# Final.net
KiCad netlist of a schematic drawn in Altium Designer
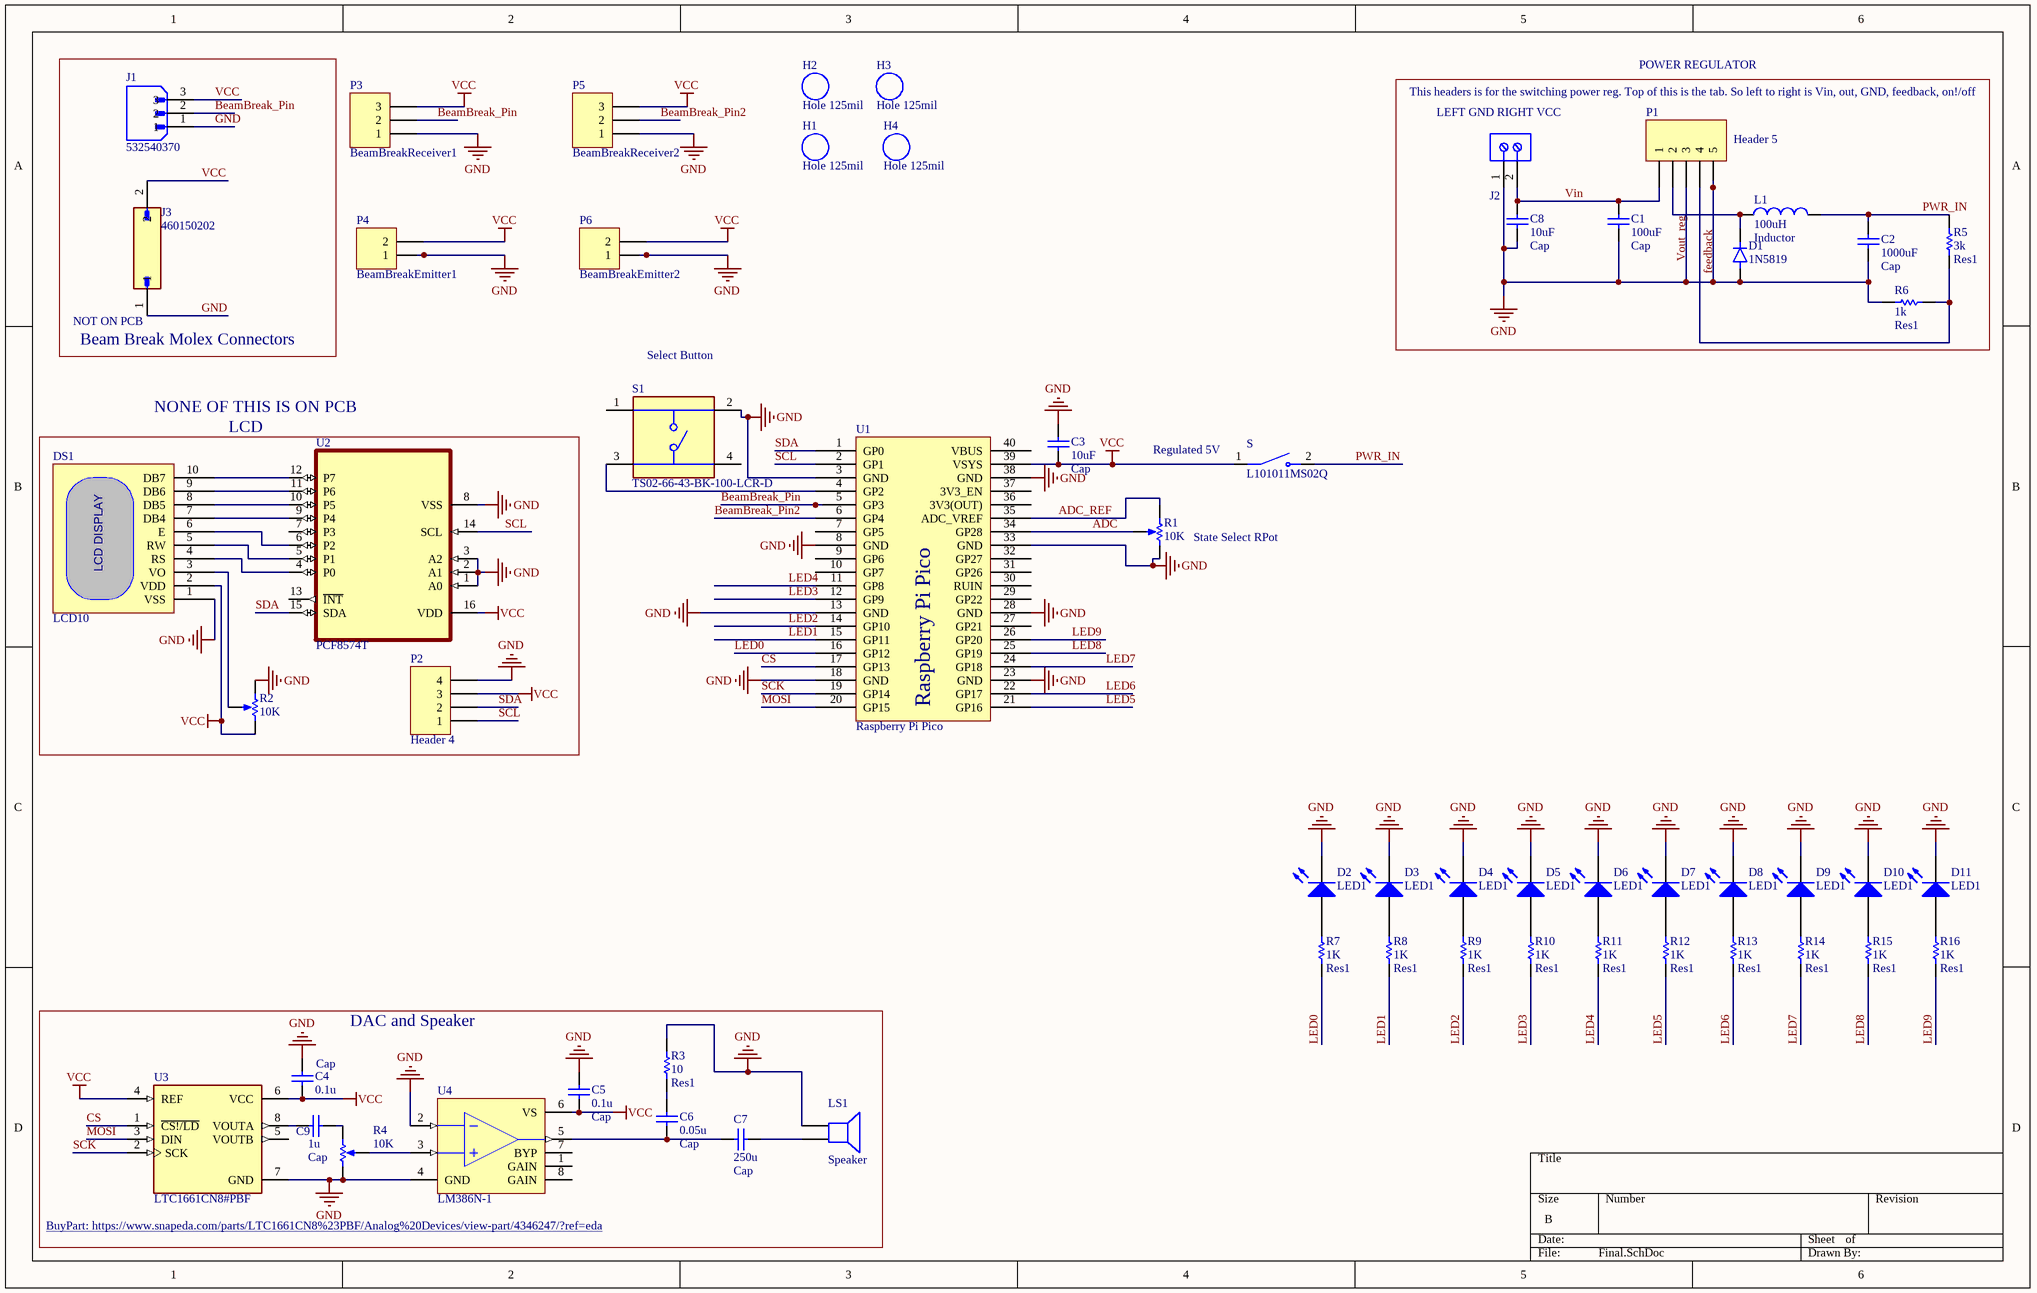
[diagram p0: Final.SchDoc]

(export (version "E")
  (design (tool "Eeschema 10.0.6"))
  (components
    (comp (ref "C1")
      (value "Cap")
      (footprint "RAD-0.3")
      (description "Capacitor")
      (fields (field (name "ALTIUM_VALUE") "100uF") (field (name "PUBLISHER") "Altium Limited"))
      (libsource (lib "Miscellaneous Devices") (part "Cap"))
    )
    (comp (ref "C2")
      (value "Cap")
      (footprint "RAD-0.3")
      (description "Capacitor")
      (fields (field (name "ALTIUM_VALUE") "1000uF") (field (name "PUBLISHER") "Altium Limited"))
      (libsource (lib "Miscellaneous Devices") (part "Cap"))
    )
    (comp (ref "C3")
      (value "Cap")
      (footprint "RAD-0.3")
      (description "Capacitor")
      (fields (field (name "ALTIUM_VALUE") "10uF") (field (name "PUBLISHER") "Altium Limited"))
      (libsource (lib "Miscellaneous Devices") (part "Cap"))
    )
    (comp (ref "C4")
      (value "Cap")
      (footprint "RAD-0.3")
      (description "Capacitor")
      (fields (field (name "ALTIUM_VALUE") "0.1u") (field (name "PUBLISHER") "Altium Limited"))
      (libsource (lib "Miscellaneous Devices") (part "Cap"))
    )
    (comp (ref "C5")
      (value "Cap")
      (footprint "RAD-0.3")
      (description "Capacitor")
      (fields (field (name "ALTIUM_VALUE") "0.1u") (field (name "PUBLISHER") "Altium Limited"))
      (libsource (lib "Miscellaneous Devices") (part "Cap"))
    )
    (comp (ref "C6")
      (value "Cap")
      (footprint "RAD-0.3")
      (description "Capacitor")
      (fields (field (name "ALTIUM_VALUE") "0.05u") (field (name "PUBLISHER") "Altium Limited"))
      (libsource (lib "Miscellaneous Devices") (part "Cap"))
    )
    (comp (ref "C7")
      (value "Cap")
      (footprint "RAD-0.3")
      (description "Capacitor")
      (fields (field (name "ALTIUM_VALUE") "250u") (field (name "PUBLISHER") "Altium Limited"))
      (libsource (lib "Miscellaneous Devices") (part "Cap"))
    )
    (comp (ref "C8")
      (value "Cap")
      (footprint "RAD-0.3")
      (description "Capacitor")
      (fields (field (name "ALTIUM_VALUE") "10uF") (field (name "PUBLISHER") "Altium Limited"))
      (libsource (lib "Miscellaneous Devices") (part "Cap"))
    )
    (comp (ref "C9")
      (value "Cap")
      (footprint "RAD-0.3")
      (description "Capacitor")
      (fields (field (name "ALTIUM_VALUE") "1u") (field (name "PUBLISHER") "Altium Limited"))
      (libsource (lib "Miscellaneous Devices") (part "Cap"))
    )
    (comp (ref "D1")
      (value "1N5819")
      (footprint "DIOAD1036W78L470D235")
      (description "1A, 40V, Planar Schottky")
      (fields (field (name "MF") "Taiwan Semiconductor"))
      (libsource (lib "1N5819") (part "1N5819"))
    )
    (comp (ref "D2")
      (value "LED1")
      (footprint "LED-1")
      (description "Typical RED GaAs LED")
      (fields (field (name "PUBLISHER") "Altium Limited"))
      (libsource (lib "Miscellaneous Devices") (part "LED1"))
    )
    (comp (ref "D3")
      (value "LED1")
      (footprint "LED-1")
      (description "Typical RED GaAs LED")
      (fields (field (name "PUBLISHER") "Altium Limited"))
      (libsource (lib "Miscellaneous Devices") (part "LED1"))
    )
    (comp (ref "D4")
      (value "LED1")
      (footprint "LED-1")
      (description "Typical RED GaAs LED")
      (fields (field (name "PUBLISHER") "Altium Limited"))
      (libsource (lib "Miscellaneous Devices") (part "LED1"))
    )
    (comp (ref "D5")
      (value "LED1")
      (footprint "LED-1")
      (description "Typical RED GaAs LED")
      (fields (field (name "PUBLISHER") "Altium Limited"))
      (libsource (lib "Miscellaneous Devices") (part "LED1"))
    )
    (comp (ref "D6")
      (value "LED1")
      (footprint "LED-1")
      (description "Typical RED GaAs LED")
      (fields (field (name "PUBLISHER") "Altium Limited"))
      (libsource (lib "Miscellaneous Devices") (part "LED1"))
    )
    (comp (ref "D7")
      (value "LED1")
      (footprint "LED-1")
      (description "Typical RED GaAs LED")
      (fields (field (name "PUBLISHER") "Altium Limited"))
      (libsource (lib "Miscellaneous Devices") (part "LED1"))
    )
    (comp (ref "D8")
      (value "LED1")
      (footprint "LED-1")
      (description "Typical RED GaAs LED")
      (fields (field (name "PUBLISHER") "Altium Limited"))
      (libsource (lib "Miscellaneous Devices") (part "LED1"))
    )
    (comp (ref "D9")
      (value "LED1")
      (footprint "LED-1")
      (description "Typical RED GaAs LED")
      (fields (field (name "PUBLISHER") "Altium Limited"))
      (libsource (lib "Miscellaneous Devices") (part "LED1"))
    )
    (comp (ref "D10")
      (value "LED1")
      (footprint "LED-1")
      (description "Typical RED GaAs LED")
      (fields (field (name "PUBLISHER") "Altium Limited"))
      (libsource (lib "Miscellaneous Devices") (part "LED1"))
    )
    (comp (ref "D11")
      (value "LED1")
      (footprint "LED-1")
      (description "Typical RED GaAs LED")
      (fields (field (name "PUBLISHER") "Altium Limited"))
      (libsource (lib "Miscellaneous Devices") (part "LED1"))
    )
    (comp (ref "DS1") (value "LCD10") (footprint "HDR1X10") (libsource (lib "ECE Lib 22") (part "LCD10")))
    (comp (ref "H1")
      (value "Hole 125mil")
      (footprint "Hole 125mil")
      (libsource (lib "ECE Lib 22") (part "Hole 125mil"))
    )
    (comp (ref "H2")
      (value "Hole 125mil")
      (footprint "Hole 125mil")
      (libsource (lib "ECE Lib 22") (part "Hole 125mil"))
    )
    (comp (ref "H3")
      (value "Hole 125mil")
      (footprint "Hole 125mil")
      (libsource (lib "ECE Lib 22") (part "Hole 125mil"))
    )
    (comp (ref "H4")
      (value "Hole 125mil")
      (footprint "Hole 125mil")
      (libsource (lib "ECE Lib 22") (part "Hole 125mil"))
    )
    (comp (ref "J1")
      (value "532540370")
      (footprint "MOLEX_532540370")
      (libsource (lib "532540370") (part "532540370"))
    )
    (comp (ref "J2")
      (value "691137710002")
      (footprint "691137710002")
      (description "WR-TBL Series 1377 Horizontal Entry, THT, pitch 5mm, 2p")
      (fields (field (name "MANUFACTURER") "Wurth Elektronik"))
      (libsource (lib "Altium_WR-TBL_rev23f") (part "691137710002"))
    )
    (comp (ref "J3")
      (value "460150202")
      (footprint "MOLEX_460150202")
      (description "Conn Power HDR 2 POS 4.2mm Solder ST Thru-Hole 2 Terminal 1 Port Mini-Fit Jr Bag")
      (libsource (lib "460150202") (part "460150202"))
    )
    (comp (ref "L1")
      (value "Inductor")
      (footprint "0402-A")
      (fields (field (name "ALTIUM_VALUE") "100uH") (field (name "PUBLISHER") "Altium Limited"))
      (libsource (lib "Miscellaneous Devices") (part "Inductor"))
    )
    (comp (ref "LS1")
      (value "Speaker")
      (footprint "PIN2")
      (description "Loudspeaker")
      (fields (field (name "PUBLISHER") "Altium Limited"))
      (libsource (lib "Miscellaneous Devices") (part "Speaker"))
    )
    (comp (ref "P1")
      (value "Header 5")
      (footprint "HDR1X5")
      (description "Header, 5-Pin")
      (fields (field (name "PUBLISHER") "Altium Limited"))
      (libsource (lib "Miscellaneous Connectors") (part "Header 5"))
    )
    (comp (ref "P2")
      (value "Header 4")
      (footprint "HDR1X4")
      (description "Header, 4-Pin")
      (fields (field (name "PUBLISHER") "Altium Limited"))
      (libsource (lib "Miscellaneous Connectors") (part "Header 4"))
    )
    (comp (ref "P3")
      (value "BeamBreakReceiver1")
      (footprint "HDR1X3")
      (description "Header, 3-Pin")
      (fields (field (name "PUBLISHER") "Altium Limited"))
      (libsource (lib "Miscellaneous Connectors") (part "Header 3"))
    )
    (comp (ref "P4")
      (value "BeamBreakEmitter1")
      (footprint "HDR1X2H")
      (description "Header, 2-Pin, Right Angle")
      (fields (field (name "PUBLISHER") "Altium Limited"))
      (libsource (lib "Miscellaneous Connectors") (part "Header 2H"))
    )
    (comp (ref "P5")
      (value "BeamBreakReceiver2")
      (footprint "HDR1X3")
      (description "Header, 3-Pin")
      (fields (field (name "PUBLISHER") "Altium Limited"))
      (libsource (lib "Miscellaneous Connectors") (part "Header 3"))
    )
    (comp (ref "P6")
      (value "BeamBreakEmitter2")
      (footprint "HDR1X2H")
      (description "Header, 2-Pin, Right Angle")
      (fields (field (name "PUBLISHER") "Altium Limited"))
      (libsource (lib "Miscellaneous Connectors") (part "Header 2H"))
    )
    (comp (ref "R1")
      (value "10K")
      (footprint "POT inline wide")
      (description "Potentiometer")
      (fields (field (name "Comment") "RPot_1") (field (name "PUBLISHER") "Altium Limited"))
      (libsource (lib "ECE Lib 22") (part "RPot_3"))
    )
    (comp (ref "R2")
      (value "10K")
      (footprint "POT OFFSET 200")
      (description "Potentiometer")
      (fields (field (name "Comment") "RPot_3") (field (name "PUBLISHER") "Altium Limited"))
      (libsource (lib "ECE Lib 22") (part "RPot"))
    )
    (comp (ref "R3")
      (value "Res1")
      (footprint "AXIAL-0.3")
      (description "Resistor")
      (fields (field (name "ALTIUM_VALUE") "10") (field (name "PUBLISHER") "Altium Limited"))
      (libsource (lib "Miscellaneous Devices") (part "Res1"))
    )
    (comp (ref "R4")
      (value "10K")
      (footprint "POT inline wide")
      (description "Potentiometer")
      (fields (field (name "Comment") "RPot_1") (field (name "PUBLISHER") "Altium Limited"))
      (libsource (lib "ECE Lib 22") (part "RPot_3"))
    )
    (comp (ref "R5")
      (value "Res1")
      (footprint "AXIAL-0.3")
      (description "Resistor")
      (fields (field (name "ALTIUM_VALUE") "3k") (field (name "PUBLISHER") "Altium Limited"))
      (libsource (lib "Miscellaneous Devices") (part "Res1"))
    )
    (comp (ref "R6")
      (value "Res1")
      (footprint "AXIAL-0.3")
      (description "Resistor")
      (fields (field (name "ALTIUM_VALUE") "1k") (field (name "PUBLISHER") "Altium Limited"))
      (libsource (lib "Miscellaneous Devices") (part "Res1"))
    )
    (comp (ref "R7")
      (value "Res1")
      (footprint "AXIAL-0.3")
      (description "Resistor")
      (fields (field (name "ALTIUM_VALUE") "1K") (field (name "PUBLISHER") "Altium Limited"))
      (libsource (lib "Miscellaneous Devices") (part "Res1"))
    )
    (comp (ref "R8")
      (value "Res1")
      (footprint "AXIAL-0.3")
      (description "Resistor")
      (fields (field (name "ALTIUM_VALUE") "1K") (field (name "PUBLISHER") "Altium Limited"))
      (libsource (lib "Miscellaneous Devices") (part "Res1"))
    )
    (comp (ref "R9")
      (value "Res1")
      (footprint "AXIAL-0.3")
      (description "Resistor")
      (fields (field (name "ALTIUM_VALUE") "1K") (field (name "PUBLISHER") "Altium Limited"))
      (libsource (lib "Miscellaneous Devices") (part "Res1"))
    )
    (comp (ref "R10")
      (value "Res1")
      (footprint "AXIAL-0.3")
      (description "Resistor")
      (fields (field (name "ALTIUM_VALUE") "1K") (field (name "PUBLISHER") "Altium Limited"))
      (libsource (lib "Miscellaneous Devices") (part "Res1"))
    )
    (comp (ref "R11")
      (value "Res1")
      (footprint "AXIAL-0.3")
      (description "Resistor")
      (fields (field (name "ALTIUM_VALUE") "1K") (field (name "PUBLISHER") "Altium Limited"))
      (libsource (lib "Miscellaneous Devices") (part "Res1"))
    )
    (comp (ref "R12")
      (value "Res1")
      (footprint "AXIAL-0.3")
      (description "Resistor")
      (fields (field (name "ALTIUM_VALUE") "1K") (field (name "PUBLISHER") "Altium Limited"))
      (libsource (lib "Miscellaneous Devices") (part "Res1"))
    )
    (comp (ref "R13")
      (value "Res1")
      (footprint "AXIAL-0.3")
      (description "Resistor")
      (fields (field (name "ALTIUM_VALUE") "1K") (field (name "PUBLISHER") "Altium Limited"))
      (libsource (lib "Miscellaneous Devices") (part "Res1"))
    )
    (comp (ref "R14")
      (value "Res1")
      (footprint "AXIAL-0.3")
      (description "Resistor")
      (fields (field (name "ALTIUM_VALUE") "1K") (field (name "PUBLISHER") "Altium Limited"))
      (libsource (lib "Miscellaneous Devices") (part "Res1"))
    )
    (comp (ref "R15")
      (value "Res1")
      (footprint "AXIAL-0.3")
      (description "Resistor")
      (fields (field (name "ALTIUM_VALUE") "1K") (field (name "PUBLISHER") "Altium Limited"))
      (libsource (lib "Miscellaneous Devices") (part "Res1"))
    )
    (comp (ref "R16")
      (value "Res1")
      (footprint "AXIAL-0.3")
      (description "Resistor")
      (fields (field (name "ALTIUM_VALUE") "1K") (field (name "PUBLISHER") "Altium Limited"))
      (libsource (lib "Miscellaneous Devices") (part "Res1"))
    )
    (comp (ref "S")
      (value "L101011MS02Q")
      (footprint "SW_L101011MS02Q")
      (description "Slide Switch SPST Through Hole")
      (fields (field (name "MF") "C&K"))
      (libsource (lib "L101011MS02Q") (part "L101011MS02Q"))
    )
    (comp (ref "S1")
      (value "TS02-66-43-BK-100-LCR-D")
      (footprint "SW_TS02-66-43-BK-100-LCR-D")
      (description "6 x 6 mm, 4.3 mm Actuator Height, 100 gf, Black, Long Crimped, Through Hole, SPST, Tactile Switch")
      (fields (field (name "MF") "Same Sky"))
      (libsource (lib "TS02-66-43-BK-100-LCR-D") (part "TS02-66-43-BK-100-LCR-D"))
    )
    (comp (ref "U1")
      (value "Raspberry Pi Pico")
      (footprint "Raspberry Pi Pico")
      (libsource (lib "ECE Lib 22") (part "Raspberry Pi Pico"))
    )
    (comp (ref "U2")
      (value "PCF8574T")
      (footprint "SOIC127P1032X265-16N")
      (description "I/O Expander 8 IÂ²C 100 kHz 20-SSOP")
      (fields (field (name "MF") "NXP Semiconductors"))
      (libsource (lib "PCF8574T") (part "PCF8574T"))
    )
    (comp (ref "U3")
      (value "LTC1661CN8#PBF")
      (footprint "DIP794W45P254L1016H393Q8")
      (description "10 Bit Digital to Analog Converter 2 8-PDIP")
      (fields
        (field (name "MF") "Analog Devices")
        (field (name "BUYPART") "https://www.snapeda.com/parts/LTC1661CN8%23PBF/Analog%20Devices/view-part/4346247/?ref=eda")
      )
      (libsource (lib "LTC1661CN8_PBF") (part "LTC1661CN8#PBF"))
    )
    (comp (ref "U4")
      (value "LM386N-1")
      (footprint "DIP-8")
      (description "Low-Voltage Audio Power Amplifier")
      (fields (field (name "PUBLISHER") "Altium Limited"))
      (libsource (lib "ECE Lib 22") (part "LM386N-1"))
    )
  )
  (nets
    (net (code "1") (name "/ADC") (class "Default")
      (node (ref "R1") (pin "2") (pinfunction "TAP_2") (pintype "passive"))
      (node (ref "U1") (pin "34") (pinfunction "GP28_34") (pintype "passive"))
    )
    (net (code "2") (name "/ADC_REF") (class "Default")
      (node (ref "R1") (pin "1") (pinfunction "TOP_1") (pintype "passive"))
      (node (ref "U1") (pin "35") (pinfunction "ADC_VREF_35") (pintype "passive"))
    )
    (net (code "3") (name "/BeamBreak_Pin") (class "Default")
      (node (ref "J1") (pin "2") (pinfunction "2_2") (pintype "passive"))
      (node (ref "P3") (pin "2") (pinfunction "2_2") (pintype "passive"))
      (node (ref "U1") (pin "5") (pinfunction "GP3_5") (pintype "passive"))
    )
    (net (code "4") (name "/BeamBreak_Pin2") (class "Default")
      (node (ref "P5") (pin "2") (pinfunction "2_2") (pintype "passive"))
      (node (ref "U1") (pin "6") (pinfunction "GP4_6") (pintype "passive"))
    )
    (net (code "5") (name "/CS") (class "Default")
      (node (ref "U1") (pin "17") (pinfunction "GP13_17") (pintype "passive"))
      (node (ref "U3") (pin "1") (pinfunction "~{CS!/LD}_1") (pintype "input"))
    )
    (net (code "6") (name "/LED0") (class "Default")
      (node (ref "R7") (pin "1") (pinfunction "1_1") (pintype "passive"))
      (node (ref "U1") (pin "16") (pinfunction "GP12_16") (pintype "passive"))
    )
    (net (code "7") (name "/LED1") (class "Default")
      (node (ref "R8") (pin "1") (pinfunction "1_1") (pintype "passive"))
      (node (ref "U1") (pin "15") (pinfunction "GP11_15") (pintype "passive"))
    )
    (net (code "8") (name "/LED2") (class "Default")
      (node (ref "R9") (pin "1") (pinfunction "1_1") (pintype "passive"))
      (node (ref "U1") (pin "14") (pinfunction "GP10_14") (pintype "passive"))
    )
    (net (code "9") (name "/LED3") (class "Default")
      (node (ref "R10") (pin "1") (pinfunction "1_1") (pintype "passive"))
      (node (ref "U1") (pin "12") (pinfunction "GP9_12") (pintype "passive"))
    )
    (net (code "10") (name "/LED4") (class "Default")
      (node (ref "R11") (pin "1") (pinfunction "1_1") (pintype "passive"))
      (node (ref "U1") (pin "11") (pinfunction "GP8_11") (pintype "passive"))
    )
    (net (code "11") (name "/LED5") (class "Default")
      (node (ref "R12") (pin "1") (pinfunction "1_1") (pintype "passive"))
      (node (ref "U1") (pin "21") (pinfunction "GP16_21") (pintype "passive"))
    )
    (net (code "12") (name "/LED6") (class "Default")
      (node (ref "R13") (pin "1") (pinfunction "1_1") (pintype "passive"))
      (node (ref "U1") (pin "22") (pinfunction "GP17_22") (pintype "passive"))
    )
    (net (code "13") (name "/LED7") (class "Default")
      (node (ref "R14") (pin "1") (pinfunction "1_1") (pintype "passive"))
      (node (ref "U1") (pin "24") (pinfunction "GP18_24") (pintype "passive"))
    )
    (net (code "14") (name "/LED8") (class "Default")
      (node (ref "R15") (pin "1") (pinfunction "1_1") (pintype "passive"))
      (node (ref "U1") (pin "25") (pinfunction "GP19_25") (pintype "passive"))
    )
    (net (code "15") (name "/LED9") (class "Default")
      (node (ref "R16") (pin "1") (pinfunction "1_1") (pintype "passive"))
      (node (ref "U1") (pin "26") (pinfunction "GP20_26") (pintype "passive"))
    )
    (net (code "16") (name "/MOSI") (class "Default")
      (node (ref "U1") (pin "20") (pinfunction "GP15_20") (pintype "passive"))
      (node (ref "U3") (pin "3") (pinfunction "DIN_3") (pintype "input"))
    )
    (net (code "17") (name "/PWR_IN") (class "Default")
      (node (ref "C2") (pin "2") (pinfunction "2_2") (pintype "passive"))
      (node (ref "L1") (pin "2") (pinfunction "2_2") (pintype "passive"))
      (node (ref "R5") (pin "2") (pinfunction "2_2") (pintype "passive"))
      (node (ref "S") (pin "2") (pinfunction "2_2") (pintype "passive"))
    )
    (net (code "18") (name "/SCK") (class "Default")
      (node (ref "U1") (pin "19") (pinfunction "GP14_19") (pintype "passive"))
      (node (ref "U3") (pin "2") (pinfunction "SCK_2") (pintype "input"))
    )
    (net (code "19") (name "/SCL") (class "Default")
      (node (ref "P2") (pin "1") (pinfunction "1_1") (pintype "passive"))
      (node (ref "U1") (pin "2") (pinfunction "GP1_2") (pintype "passive"))
      (node (ref "U2") (pin "14") (pinfunction "SCL_14") (pintype "input"))
    )
    (net (code "20") (name "/SDA") (class "Default")
      (node (ref "P2") (pin "2") (pinfunction "2_2") (pintype "passive"))
      (node (ref "U1") (pin "1") (pinfunction "GP0_1") (pintype "passive"))
      (node (ref "U2") (pin "15") (pinfunction "SDA_15") (pintype "bidirectional"))
    )
    (net (code "21") (name "/Vin") (class "Default")
      (node (ref "C1") (pin "1") (pinfunction "1_1") (pintype "passive"))
      (node (ref "C8") (pin "2") (pinfunction "2_2") (pintype "passive"))
      (node (ref "J2") (pin "2") (pinfunction "2_2") (pintype "passive"))
      (node (ref "P1") (pin "1") (pinfunction "1_1") (pintype "passive"))
    )
    (net (code "22") (name "/Vout_reg") (class "Default")
      (node (ref "D1") (pin "C") (pinfunction "K_C") (pintype "passive"))
      (node (ref "L1") (pin "1") (pinfunction "1_1") (pintype "passive"))
      (node (ref "P1") (pin "2") (pinfunction "2_2") (pintype "passive"))
    )
    (net (code "23") (name "/feedback") (class "Default")
      (node (ref "P1") (pin "4") (pinfunction "4_4") (pintype "passive"))
      (node (ref "R5") (pin "1") (pinfunction "1_1") (pintype "passive"))
      (node (ref "R6") (pin "2") (pinfunction "2_2") (pintype "passive"))
    )
    (net (code "24") (name "GND") (class "Default")
      (node (ref "C1") (pin "2") (pinfunction "2_2") (pintype "passive"))
      (node (ref "C2") (pin "1") (pinfunction "1_1") (pintype "passive"))
      (node (ref "C3") (pin "1") (pinfunction "1_1") (pintype "passive"))
      (node (ref "C4") (pin "2") (pinfunction "2_2") (pintype "passive"))
      (node (ref "C5") (pin "2") (pinfunction "2_2") (pintype "passive"))
      (node (ref "C8") (pin "1") (pinfunction "1_1") (pintype "passive"))
      (node (ref "D1") (pin "A") (pinfunction "A_A") (pintype "passive"))
      (node (ref "D10") (pin "2") (pinfunction "K_2") (pintype "passive"))
      (node (ref "D11") (pin "2") (pinfunction "K_2") (pintype "passive"))
      (node (ref "D2") (pin "2") (pinfunction "K_2") (pintype "passive"))
      (node (ref "D3") (pin "2") (pinfunction "K_2") (pintype "passive"))
      (node (ref "D4") (pin "2") (pinfunction "K_2") (pintype "passive"))
      (node (ref "D5") (pin "2") (pinfunction "K_2") (pintype "passive"))
      (node (ref "D6") (pin "2") (pinfunction "K_2") (pintype "passive"))
      (node (ref "D7") (pin "2") (pinfunction "K_2") (pintype "passive"))
      (node (ref "D8") (pin "2") (pinfunction "K_2") (pintype "passive"))
      (node (ref "D9") (pin "2") (pinfunction "K_2") (pintype "passive"))
      (node (ref "DS1") (pin "1") (pinfunction "VSS_1") (pintype "passive"))
      (node (ref "J1") (pin "1") (pinfunction "1_1") (pintype "passive"))
      (node (ref "J2") (pin "1") (pinfunction "1_1") (pintype "passive"))
      (node (ref "J3") (pin "1") (pinfunction "1_1") (pintype "passive"))
      (node (ref "LS1") (pin "1") (pinfunction "1_1") (pintype "passive"))
      (node (ref "P1") (pin "3") (pinfunction "3_3") (pintype "passive"))
      (node (ref "P1") (pin "5") (pinfunction "5_5") (pintype "passive"))
      (node (ref "P2") (pin "4") (pinfunction "4_4") (pintype "passive"))
      (node (ref "P3") (pin "1") (pinfunction "1_1") (pintype "passive"))
      (node (ref "P4") (pin "1") (pinfunction "1_1") (pintype "passive"))
      (node (ref "P5") (pin "1") (pinfunction "1_1") (pintype "passive"))
      (node (ref "P6") (pin "1") (pinfunction "1_1") (pintype "passive"))
      (node (ref "R1") (pin "3") (pinfunction "BOT_3") (pintype "passive"))
      (node (ref "R2") (pin "1") (pinfunction "TOP_1") (pintype "passive"))
      (node (ref "R3") (pin "2") (pinfunction "2_2") (pintype "passive"))
      (node (ref "R4") (pin "1") (pinfunction "TOP_1") (pintype "passive"))
      (node (ref "R6") (pin "1") (pinfunction "1_1") (pintype "passive"))
      (node (ref "S1") (pin "2") (pinfunction "2_2") (pintype "passive"))
      (node (ref "U1") (pin "13") (pinfunction "GND_13") (pintype "passive"))
      (node (ref "U1") (pin "18") (pinfunction "GND_18") (pintype "passive"))
      (node (ref "U1") (pin "23") (pinfunction "GND_23") (pintype "passive"))
      (node (ref "U1") (pin "28") (pinfunction "GND_28") (pintype "passive"))
      (node (ref "U1") (pin "3") (pinfunction "GND_3") (pintype "passive"))
      (node (ref "U1") (pin "33") (pinfunction "GND_33") (pintype "passive"))
      (node (ref "U1") (pin "38") (pinfunction "GND_38") (pintype "passive"))
      (node (ref "U1") (pin "8") (pinfunction "GND_8") (pintype "passive"))
      (node (ref "U2") (pin "1") (pinfunction "A0_1") (pintype "input"))
      (node (ref "U2") (pin "2") (pinfunction "A1_2") (pintype "input"))
      (node (ref "U2") (pin "3") (pinfunction "A2_3") (pintype "input"))
      (node (ref "U2") (pin "8") (pinfunction "VSS_8") (pintype "passive"))
      (node (ref "U3") (pin "7") (pinfunction "GND_7") (pintype "power_in"))
      (node (ref "U4") (pin "2") (pinfunction "IN-_2") (pintype "input"))
      (node (ref "U4") (pin "4") (pinfunction "GND_4") (pintype "power_in"))
    )
    (net (code "25") (name "Net-(C6-Pad2)") (class "Default")
      (node (ref "C6") (pin "2") (pinfunction "2_2") (pintype "passive"))
      (node (ref "R3") (pin "1") (pinfunction "1_1") (pintype "passive"))
    )
    (net (code "26") (name "Net-(C7-Pad2)") (class "Default")
      (node (ref "C7") (pin "2") (pinfunction "2_2") (pintype "passive"))
      (node (ref "LS1") (pin "2") (pinfunction "2_2") (pintype "passive"))
    )
    (net (code "27") (name "Net-(D2-A)") (class "Default")
      (node (ref "D2") (pin "1") (pinfunction "A_1") (pintype "passive"))
      (node (ref "R7") (pin "2") (pinfunction "2_2") (pintype "passive"))
    )
    (net (code "28") (name "Net-(D3-A)") (class "Default")
      (node (ref "D3") (pin "1") (pinfunction "A_1") (pintype "passive"))
      (node (ref "R8") (pin "2") (pinfunction "2_2") (pintype "passive"))
    )
    (net (code "29") (name "Net-(D4-A)") (class "Default")
      (node (ref "D4") (pin "1") (pinfunction "A_1") (pintype "passive"))
      (node (ref "R9") (pin "2") (pinfunction "2_2") (pintype "passive"))
    )
    (net (code "30") (name "Net-(D5-A)") (class "Default")
      (node (ref "D5") (pin "1") (pinfunction "A_1") (pintype "passive"))
      (node (ref "R10") (pin "2") (pinfunction "2_2") (pintype "passive"))
    )
    (net (code "31") (name "Net-(D6-A)") (class "Default")
      (node (ref "D6") (pin "1") (pinfunction "A_1") (pintype "passive"))
      (node (ref "R11") (pin "2") (pinfunction "2_2") (pintype "passive"))
    )
    (net (code "32") (name "Net-(D7-A)") (class "Default")
      (node (ref "D7") (pin "1") (pinfunction "A_1") (pintype "passive"))
      (node (ref "R12") (pin "2") (pinfunction "2_2") (pintype "passive"))
    )
    (net (code "33") (name "Net-(D8-A)") (class "Default")
      (node (ref "D8") (pin "1") (pinfunction "A_1") (pintype "passive"))
      (node (ref "R13") (pin "2") (pinfunction "2_2") (pintype "passive"))
    )
    (net (code "34") (name "Net-(D9-A)") (class "Default")
      (node (ref "D9") (pin "1") (pinfunction "A_1") (pintype "passive"))
      (node (ref "R14") (pin "2") (pinfunction "2_2") (pintype "passive"))
    )
    (net (code "35") (name "Net-(D10-A)") (class "Default")
      (node (ref "D10") (pin "1") (pinfunction "A_1") (pintype "passive"))
      (node (ref "R15") (pin "2") (pinfunction "2_2") (pintype "passive"))
    )
    (net (code "36") (name "Net-(D11-A)") (class "Default")
      (node (ref "D11") (pin "1") (pinfunction "A_1") (pintype "passive"))
      (node (ref "R16") (pin "2") (pinfunction "2_2") (pintype "passive"))
    )
    (net (code "37") (name "Net-(DS1-DB4)") (class "Default")
      (node (ref "DS1") (pin "7") (pinfunction "DB4_7") (pintype "passive"))
      (node (ref "U2") (pin "9") (pinfunction "P4_9") (pintype "bidirectional"))
    )
    (net (code "38") (name "Net-(DS1-DB5)") (class "Default")
      (node (ref "DS1") (pin "8") (pinfunction "DB5_8") (pintype "passive"))
      (node (ref "U2") (pin "10") (pinfunction "P5_10") (pintype "bidirectional"))
    )
    (net (code "39") (name "Net-(DS1-DB6)") (class "Default")
      (node (ref "DS1") (pin "9") (pinfunction "DB6_9") (pintype "passive"))
      (node (ref "U2") (pin "11") (pinfunction "P6_11") (pintype "bidirectional"))
    )
    (net (code "40") (name "Net-(DS1-DB7)") (class "Default")
      (node (ref "DS1") (pin "10") (pinfunction "DB7_10") (pintype "passive"))
      (node (ref "U2") (pin "12") (pinfunction "P7_12") (pintype "bidirectional"))
    )
    (net (code "41") (name "Net-(DS1-E)") (class "Default")
      (node (ref "DS1") (pin "6") (pinfunction "E_6") (pintype "passive"))
      (node (ref "U2") (pin "6") (pinfunction "P2_6") (pintype "bidirectional"))
    )
    (net (code "42") (name "Net-(DS1-RS)") (class "Default")
      (node (ref "DS1") (pin "4") (pinfunction "RS_4") (pintype "passive"))
      (node (ref "U2") (pin "4") (pinfunction "P0_4") (pintype "bidirectional"))
    )
    (net (code "43") (name "Net-(DS1-RW)") (class "Default")
      (node (ref "DS1") (pin "5") (pinfunction "RW_5") (pintype "passive"))
      (node (ref "U2") (pin "5") (pinfunction "P1_5") (pintype "bidirectional"))
    )
    (net (code "44") (name "Net-(DS1-VO)") (class "Default")
      (node (ref "DS1") (pin "3") (pinfunction "VO_3") (pintype "passive"))
      (node (ref "R2") (pin "2") (pinfunction "TAP_2") (pintype "passive"))
    )
    (net (code "45") (name "Net-(R4-BOT)") (class "Default")
      (node (ref "C9") (pin "1") (pinfunction "1_1") (pintype "passive"))
      (node (ref "R4") (pin "3") (pinfunction "BOT_3") (pintype "passive"))
    )
    (net (code "46") (name "Net-(R4-TAP)") (class "Default")
      (node (ref "R4") (pin "2") (pinfunction "TAP_2") (pintype "passive"))
      (node (ref "U4") (pin "3") (pinfunction "IN+_3") (pintype "input"))
    )
    (net (code "47") (name "Net-(U1-GP2)") (class "Default")
      (node (ref "S1") (pin "3") (pinfunction "3_3") (pintype "passive"))
      (node (ref "U1") (pin "4") (pinfunction "GP2_4") (pintype "passive"))
    )
    (net (code "48") (name "Net-(U3-VOUTA)") (class "Default")
      (node (ref "C9") (pin "2") (pinfunction "2_2") (pintype "passive"))
      (node (ref "U3") (pin "8") (pinfunction "VOUTA_8") (pintype "output"))
    )
    (net (code "49") (name "Net-(U4-OUT)") (class "Default")
      (node (ref "C6") (pin "1") (pinfunction "1_1") (pintype "passive"))
      (node (ref "C7") (pin "1") (pinfunction "1_1") (pintype "passive"))
      (node (ref "U4") (pin "5") (pinfunction "OUT_5") (pintype "output"))
    )
    (net (code "50") (name "VCC") (class "Default")
      (node (ref "C3") (pin "2") (pinfunction "2_2") (pintype "passive"))
      (node (ref "C4") (pin "1") (pinfunction "1_1") (pintype "passive"))
      (node (ref "C5") (pin "1") (pinfunction "1_1") (pintype "passive"))
      (node (ref "DS1") (pin "2") (pinfunction "VDD_2") (pintype "passive"))
      (node (ref "J1") (pin "3") (pinfunction "3_3") (pintype "passive"))
      (node (ref "J3") (pin "2") (pinfunction "2_2") (pintype "passive"))
      (node (ref "P2") (pin "3") (pinfunction "3_3") (pintype "passive"))
      (node (ref "P3") (pin "3") (pinfunction "3_3") (pintype "passive"))
      (node (ref "P4") (pin "2") (pinfunction "2_2") (pintype "passive"))
      (node (ref "P5") (pin "3") (pinfunction "3_3") (pintype "passive"))
      (node (ref "P6") (pin "2") (pinfunction "2_2") (pintype "passive"))
      (node (ref "R2") (pin "3") (pinfunction "BOT_3") (pintype "passive"))
      (node (ref "S") (pin "1") (pinfunction "1_1") (pintype "passive"))
      (node (ref "U1") (pin "39") (pinfunction "VSYS_39") (pintype "passive"))
      (node (ref "U2") (pin "16") (pinfunction "VDD_16") (pintype "power_in"))
      (node (ref "U3") (pin "4") (pinfunction "REF_4") (pintype "input"))
      (node (ref "U3") (pin "6") (pinfunction "VCC_6") (pintype "power_in"))
      (node (ref "U4") (pin "6") (pinfunction "VS_6") (pintype "power_in"))
    )
    (net (code "51") (name "unconnected-(S1-Pad1)") (class "Default")
      (node (ref "S1") (pin "1") (pinfunction "1_1") (pintype "passive"))
    )
    (net (code "52") (name "unconnected-(S1-Pad4)") (class "Default")
      (node (ref "S1") (pin "4") (pinfunction "4_4") (pintype "passive"))
    )
    (net (code "53") (name "unconnected-(U1-3V3(OUT)-Pad36)") (class "Default")
      (node (ref "U1") (pin "36") (pinfunction "3V3(OUT)_36") (pintype "passive"))
    )
    (net (code "54") (name "unconnected-(U1-3V3_EN-Pad37)") (class "Default")
      (node (ref "U1") (pin "37") (pinfunction "3V3_EN_37") (pintype "passive"))
    )
    (net (code "55") (name "unconnected-(U1-GP5-Pad7)") (class "Default")
      (node (ref "U1") (pin "7") (pinfunction "GP5_7") (pintype "passive"))
    )
    (net (code "56") (name "unconnected-(U1-GP6-Pad9)") (class "Default")
      (node (ref "U1") (pin "9") (pinfunction "GP6_9") (pintype "passive"))
    )
    (net (code "57") (name "unconnected-(U1-GP7-Pad10)") (class "Default")
      (node (ref "U1") (pin "10") (pinfunction "GP7_10") (pintype "passive"))
    )
    (net (code "58") (name "unconnected-(U1-GP21-Pad27)") (class "Default")
      (node (ref "U1") (pin "27") (pinfunction "GP21_27") (pintype "passive"))
    )
    (net (code "59") (name "unconnected-(U1-GP22-Pad29)") (class "Default")
      (node (ref "U1") (pin "29") (pinfunction "GP22_29") (pintype "passive"))
    )
    (net (code "60") (name "unconnected-(U1-GP26-Pad31)") (class "Default")
      (node (ref "U1") (pin "31") (pinfunction "GP26_31") (pintype "passive"))
    )
    (net (code "61") (name "unconnected-(U1-GP27-Pad32)") (class "Default")
      (node (ref "U1") (pin "32") (pinfunction "GP27_32") (pintype "passive"))
    )
    (net (code "62") (name "unconnected-(U1-RUIN-Pad30)") (class "Default")
      (node (ref "U1") (pin "30") (pinfunction "RUIN_30") (pintype "passive"))
    )
    (net (code "63") (name "unconnected-(U1-VBUS-Pad40)") (class "Default")
      (node (ref "U1") (pin "40") (pinfunction "VBUS_40") (pintype "passive"))
    )
    (net (code "64") (name "unconnected-(U2-P3-Pad7)") (class "Default")
      (node (ref "U2") (pin "7") (pinfunction "P3_7") (pintype "bidirectional"))
    )
    (net (code "65") (name "unconnected-(U2-~{INT}-Pad13)") (class "Default")
      (node (ref "U2") (pin "13") (pinfunction "~{INT}_13") (pintype "output"))
    )
    (net (code "66") (name "unconnected-(U3-VOUTB-Pad5)") (class "Default")
      (node (ref "U3") (pin "5") (pinfunction "VOUTB_5") (pintype "output"))
    )
    (net (code "67") (name "unconnected-(U4-BYP-Pad7)") (class "Default")
      (node (ref "U4") (pin "7") (pinfunction "BYP_7") (pintype "passive"))
    )
    (net (code "68") (name "unconnected-(U4-GAIN-Pad1)") (class "Default")
      (node (ref "U4") (pin "1") (pinfunction "GAIN_1") (pintype "passive"))
    )
    (net (code "69") (name "unconnected-(U4-GAIN-Pad8)") (class "Default")
      (node (ref "U4") (pin "8") (pinfunction "GAIN_8") (pintype "passive"))
    )
  )
)
